# PCB_ARDUINO_NANO.net
KiCad netlist of a schematic drawn in EAGLE
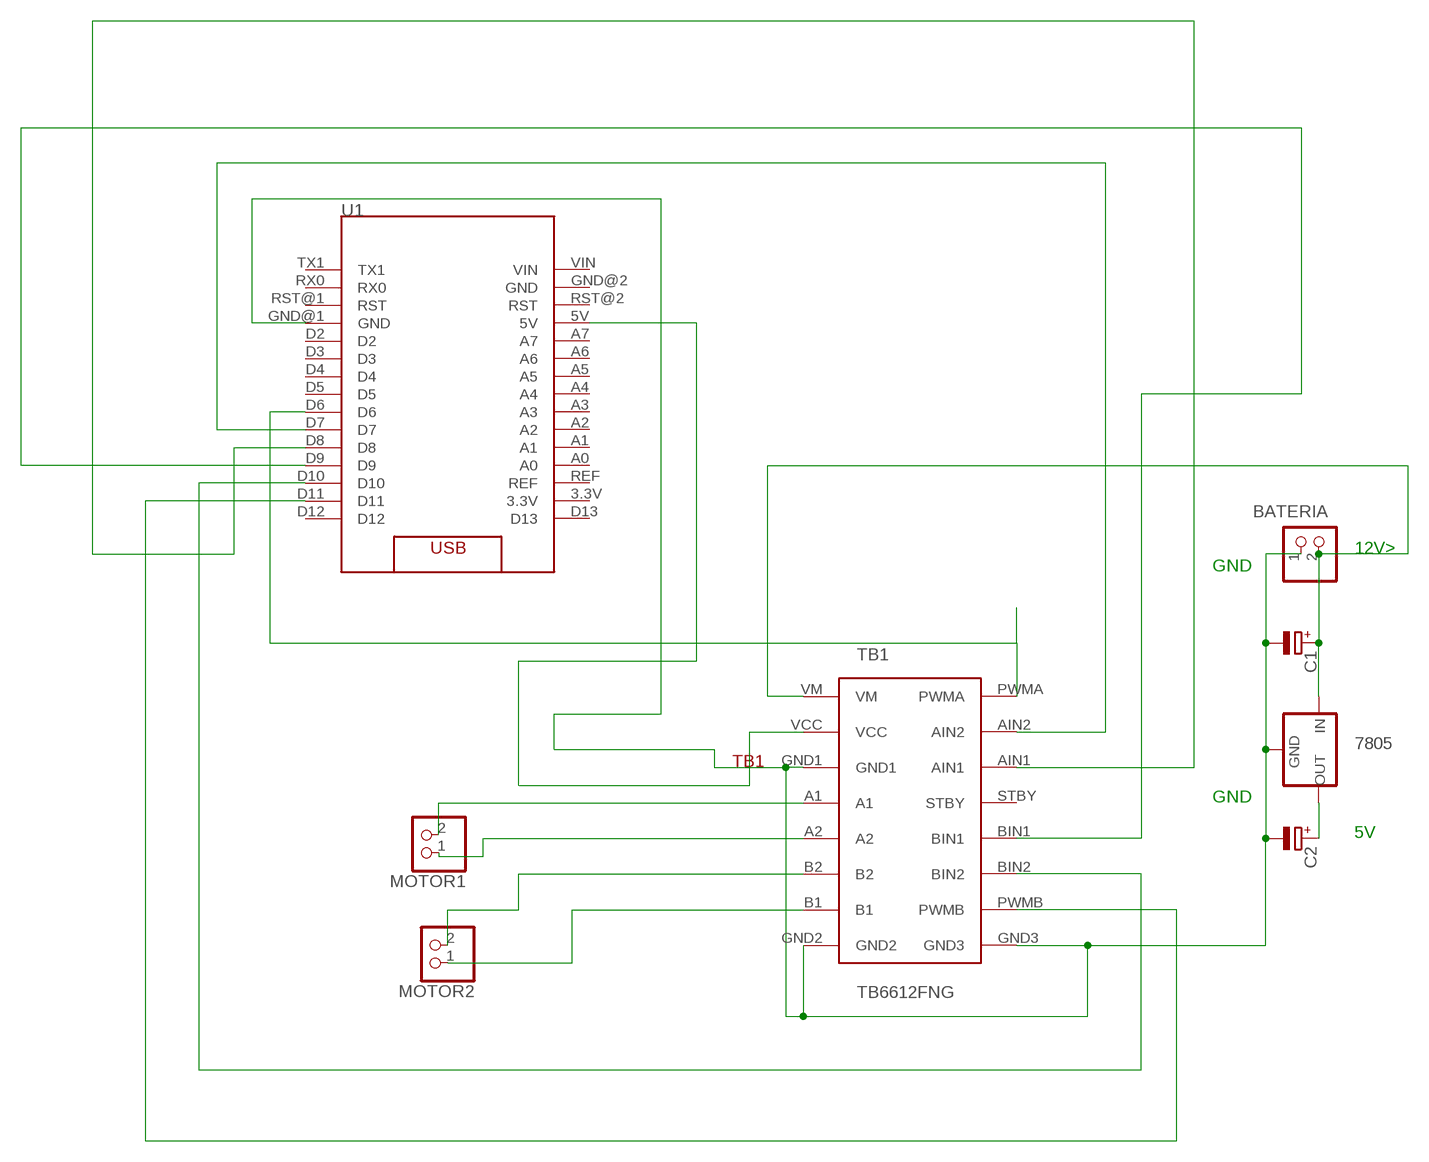
[diagram p0: schematic, sheet 1]

(export (version "E")
  (design (tool "Eeschema 10.0.6"))
  (components
    (comp (ref "7805")
      (value "78XXS")
      (footprint "eagle-import:78XXS")
      (libsource (lib "eagle-import") (part "78XXS"))
    )
    (comp (ref "BATERIA")
      (value "PINHD-1X2")
      (footprint "eagle-import:1X02")
      (libsource (lib "eagle-import") (part "PINHD-1X2"))
    )
    (comp (ref "C1")
      (value "CPOL-EUE2.5-6")
      (footprint "eagle-import:E2,5-6")
      (libsource (lib "eagle-import") (part "CPOL-EUE2.5-6"))
    )
    (comp (ref "C2")
      (value "CPOL-EUE2.5-6")
      (footprint "eagle-import:E2,5-6")
      (libsource (lib "eagle-import") (part "CPOL-EUE2.5-6"))
    )
    (comp (ref "MOTOR1")
      (value "PINHD-1X2")
      (footprint "eagle-import:1X02")
      (libsource (lib "eagle-import") (part "PINHD-1X2"))
    )
    (comp (ref "MOTOR2")
      (value "PINHD-1X2")
      (footprint "eagle-import:1X02")
      (libsource (lib "eagle-import") (part "PINHD-1X2"))
    )
    (comp (ref "TB1")
      (value "TB6612FNG")
      (footprint "eagle-import:TB6612FNG")
      (libsource (lib "eagle-import") (part "TB6612FNG"))
    )
    (comp (ref "U1")
      (value "ARDUINO_NANO")
      (footprint "eagle-import:ARDUINO_NANO")
      (libsource (lib "eagle-import") (part "ARDUINO_NANO"))
    )
  )
  (nets
    (net (code "1") (name "Net-(7805-PadGND)") (class "Default")
      (node (ref "7805") (pin "GND") (pinfunction "GND_GND") (pintype "input"))
      (node (ref "BATERIA") (pin "1") (pinfunction "1_1") (pintype "passive"))
      (node (ref "C1") (pin "-") (pinfunction "-_-") (pintype "passive"))
      (node (ref "C2") (pin "-") (pinfunction "-_-") (pintype "passive"))
      (node (ref "TB1") (pin "GND1") (pinfunction "GND1_GND1") (pintype "bidirectional"))
      (node (ref "TB1") (pin "GND2") (pinfunction "GND2_GND2") (pintype "bidirectional"))
      (node (ref "TB1") (pin "GND3") (pinfunction "GND3_GND3") (pintype "bidirectional"))
      (node (ref "U1") (pin "GND@1") (pinfunction "GND_GND@1") (pintype "bidirectional"))
    )
    (net (code "2") (name "Net-(7805-PadIN)") (class "Default")
      (node (ref "7805") (pin "IN") (pinfunction "IN_IN") (pintype "input"))
      (node (ref "BATERIA") (pin "2") (pinfunction "2_2") (pintype "passive"))
      (node (ref "C1") (pin "+") (pinfunction "+_+") (pintype "passive"))
      (node (ref "TB1") (pin "VM") (pinfunction "VM_VM") (pintype "bidirectional"))
    )
    (net (code "3") (name "Net-(7805-PadOUT)") (class "Default")
      (node (ref "7805") (pin "OUT") (pinfunction "OUT_OUT") (pintype "passive"))
      (node (ref "C2") (pin "+") (pinfunction "+_+") (pintype "passive"))
    )
    (net (code "4") (name "Net-(MOTOR1-Pad1)") (class "Default")
      (node (ref "MOTOR1") (pin "1") (pinfunction "1_1") (pintype "passive"))
      (node (ref "TB1") (pin "A2") (pinfunction "A2_A2") (pintype "bidirectional"))
    )
    (net (code "5") (name "Net-(MOTOR1-Pad2)") (class "Default")
      (node (ref "MOTOR1") (pin "2") (pinfunction "2_2") (pintype "passive"))
      (node (ref "TB1") (pin "A1") (pinfunction "A1_A1") (pintype "bidirectional"))
    )
    (net (code "6") (name "Net-(MOTOR2-Pad1)") (class "Default")
      (node (ref "MOTOR2") (pin "1") (pinfunction "1_1") (pintype "passive"))
      (node (ref "TB1") (pin "B1") (pinfunction "B1_B1") (pintype "bidirectional"))
    )
    (net (code "7") (name "Net-(MOTOR2-Pad2)") (class "Default")
      (node (ref "MOTOR2") (pin "2") (pinfunction "2_2") (pintype "passive"))
      (node (ref "TB1") (pin "B2") (pinfunction "B2_B2") (pintype "bidirectional"))
    )
    (net (code "8") (name "Net-(TB1-PadAIN1)") (class "Default")
      (node (ref "TB1") (pin "AIN1") (pinfunction "AIN1_AIN1") (pintype "bidirectional"))
      (node (ref "U1") (pin "D8") (pinfunction "D8_D8") (pintype "bidirectional"))
    )
    (net (code "9") (name "Net-(TB1-PadAIN2)") (class "Default")
      (node (ref "TB1") (pin "AIN2") (pinfunction "AIN2_AIN2") (pintype "bidirectional"))
      (node (ref "U1") (pin "D7") (pinfunction "D7_D7") (pintype "bidirectional"))
    )
    (net (code "10") (name "Net-(TB1-PadBIN1)") (class "Default")
      (node (ref "TB1") (pin "BIN1") (pinfunction "BIN1_BIN1") (pintype "bidirectional"))
      (node (ref "U1") (pin "D9") (pinfunction "D9_D9") (pintype "bidirectional"))
    )
    (net (code "11") (name "Net-(TB1-PadBIN2)") (class "Default")
      (node (ref "TB1") (pin "BIN2") (pinfunction "BIN2_BIN2") (pintype "bidirectional"))
      (node (ref "U1") (pin "D10") (pinfunction "D10_D10") (pintype "bidirectional"))
    )
    (net (code "12") (name "Net-(TB1-PadPWMA)") (class "Default")
      (node (ref "TB1") (pin "PWMA") (pinfunction "PWMA_PWMA") (pintype "bidirectional"))
      (node (ref "U1") (pin "D6") (pinfunction "D6_D6") (pintype "bidirectional"))
    )
    (net (code "13") (name "Net-(TB1-PadPWMB)") (class "Default")
      (node (ref "TB1") (pin "PWMB") (pinfunction "PWMB_PWMB") (pintype "bidirectional"))
      (node (ref "U1") (pin "D11") (pinfunction "D11_D11") (pintype "bidirectional"))
    )
    (net (code "14") (name "Net-(TB1-PadVCC)") (class "Default")
      (node (ref "TB1") (pin "VCC") (pinfunction "VCC_VCC") (pintype "bidirectional"))
      (node (ref "U1") (pin "5V") (pinfunction "5V_5V") (pintype "bidirectional"))
    )
    (net (code "15") (name "unconnected-(TB1-PadSTBY)") (class "Default")
      (node (ref "TB1") (pin "STBY") (pinfunction "STBY_STBY") (pintype "bidirectional"))
    )
    (net (code "16") (name "unconnected-(U1-GND-PadGND@2)") (class "Default")
      (node (ref "U1") (pin "GND@2") (pinfunction "GND_GND@2") (pintype "bidirectional"))
    )
    (net (code "17") (name "unconnected-(U1-Pad3.3V)") (class "Default")
      (node (ref "U1") (pin "3.3V") (pinfunction "3.3V_3.3V") (pintype "bidirectional"))
    )
    (net (code "18") (name "unconnected-(U1-PadA0)") (class "Default")
      (node (ref "U1") (pin "A0") (pinfunction "A0_A0") (pintype "bidirectional"))
    )
    (net (code "19") (name "unconnected-(U1-PadA1)") (class "Default")
      (node (ref "U1") (pin "A1") (pinfunction "A1_A1") (pintype "bidirectional"))
    )
    (net (code "20") (name "unconnected-(U1-PadA2)") (class "Default")
      (node (ref "U1") (pin "A2") (pinfunction "A2_A2") (pintype "bidirectional"))
    )
    (net (code "21") (name "unconnected-(U1-PadA3)") (class "Default")
      (node (ref "U1") (pin "A3") (pinfunction "A3_A3") (pintype "bidirectional"))
    )
    (net (code "22") (name "unconnected-(U1-PadA4)") (class "Default")
      (node (ref "U1") (pin "A4") (pinfunction "A4_A4") (pintype "bidirectional"))
    )
    (net (code "23") (name "unconnected-(U1-PadA5)") (class "Default")
      (node (ref "U1") (pin "A5") (pinfunction "A5_A5") (pintype "bidirectional"))
    )
    (net (code "24") (name "unconnected-(U1-PadA6)") (class "Default")
      (node (ref "U1") (pin "A6") (pinfunction "A6_A6") (pintype "bidirectional"))
    )
    (net (code "25") (name "unconnected-(U1-PadA7)") (class "Default")
      (node (ref "U1") (pin "A7") (pinfunction "A7_A7") (pintype "bidirectional"))
    )
    (net (code "26") (name "unconnected-(U1-PadD2)") (class "Default")
      (node (ref "U1") (pin "D2") (pinfunction "D2_D2") (pintype "bidirectional"))
    )
    (net (code "27") (name "unconnected-(U1-PadD3)") (class "Default")
      (node (ref "U1") (pin "D3") (pinfunction "D3_D3") (pintype "bidirectional"))
    )
    (net (code "28") (name "unconnected-(U1-PadD4)") (class "Default")
      (node (ref "U1") (pin "D4") (pinfunction "D4_D4") (pintype "bidirectional"))
    )
    (net (code "29") (name "unconnected-(U1-PadD5)") (class "Default")
      (node (ref "U1") (pin "D5") (pinfunction "D5_D5") (pintype "bidirectional"))
    )
    (net (code "30") (name "unconnected-(U1-PadD12)") (class "Default")
      (node (ref "U1") (pin "D12") (pinfunction "D12_D12") (pintype "bidirectional"))
    )
    (net (code "31") (name "unconnected-(U1-PadD13)") (class "Default")
      (node (ref "U1") (pin "D13") (pinfunction "D13_D13") (pintype "bidirectional"))
    )
    (net (code "32") (name "unconnected-(U1-PadREF)") (class "Default")
      (node (ref "U1") (pin "REF") (pinfunction "REF_REF") (pintype "bidirectional"))
    )
    (net (code "33") (name "unconnected-(U1-PadRX0)") (class "Default")
      (node (ref "U1") (pin "RX0") (pinfunction "RX0_RX0") (pintype "bidirectional"))
    )
    (net (code "34") (name "unconnected-(U1-PadTX1)") (class "Default")
      (node (ref "U1") (pin "TX1") (pinfunction "TX1_TX1") (pintype "bidirectional"))
    )
    (net (code "35") (name "unconnected-(U1-PadVIN)") (class "Default")
      (node (ref "U1") (pin "VIN") (pinfunction "VIN_VIN") (pintype "bidirectional"))
    )
    (net (code "36") (name "unconnected-(U1-RST-PadRST@1)") (class "Default")
      (node (ref "U1") (pin "RST@1") (pinfunction "RST_RST@1") (pintype "bidirectional"))
    )
    (net (code "37") (name "unconnected-(U1-RST-PadRST@2)") (class "Default")
      (node (ref "U1") (pin "RST@2") (pinfunction "RST_RST@2") (pintype "bidirectional"))
    )
  )
)
